# power_supply.net
KiCad netlist of a schematic drawn in Altium Designer
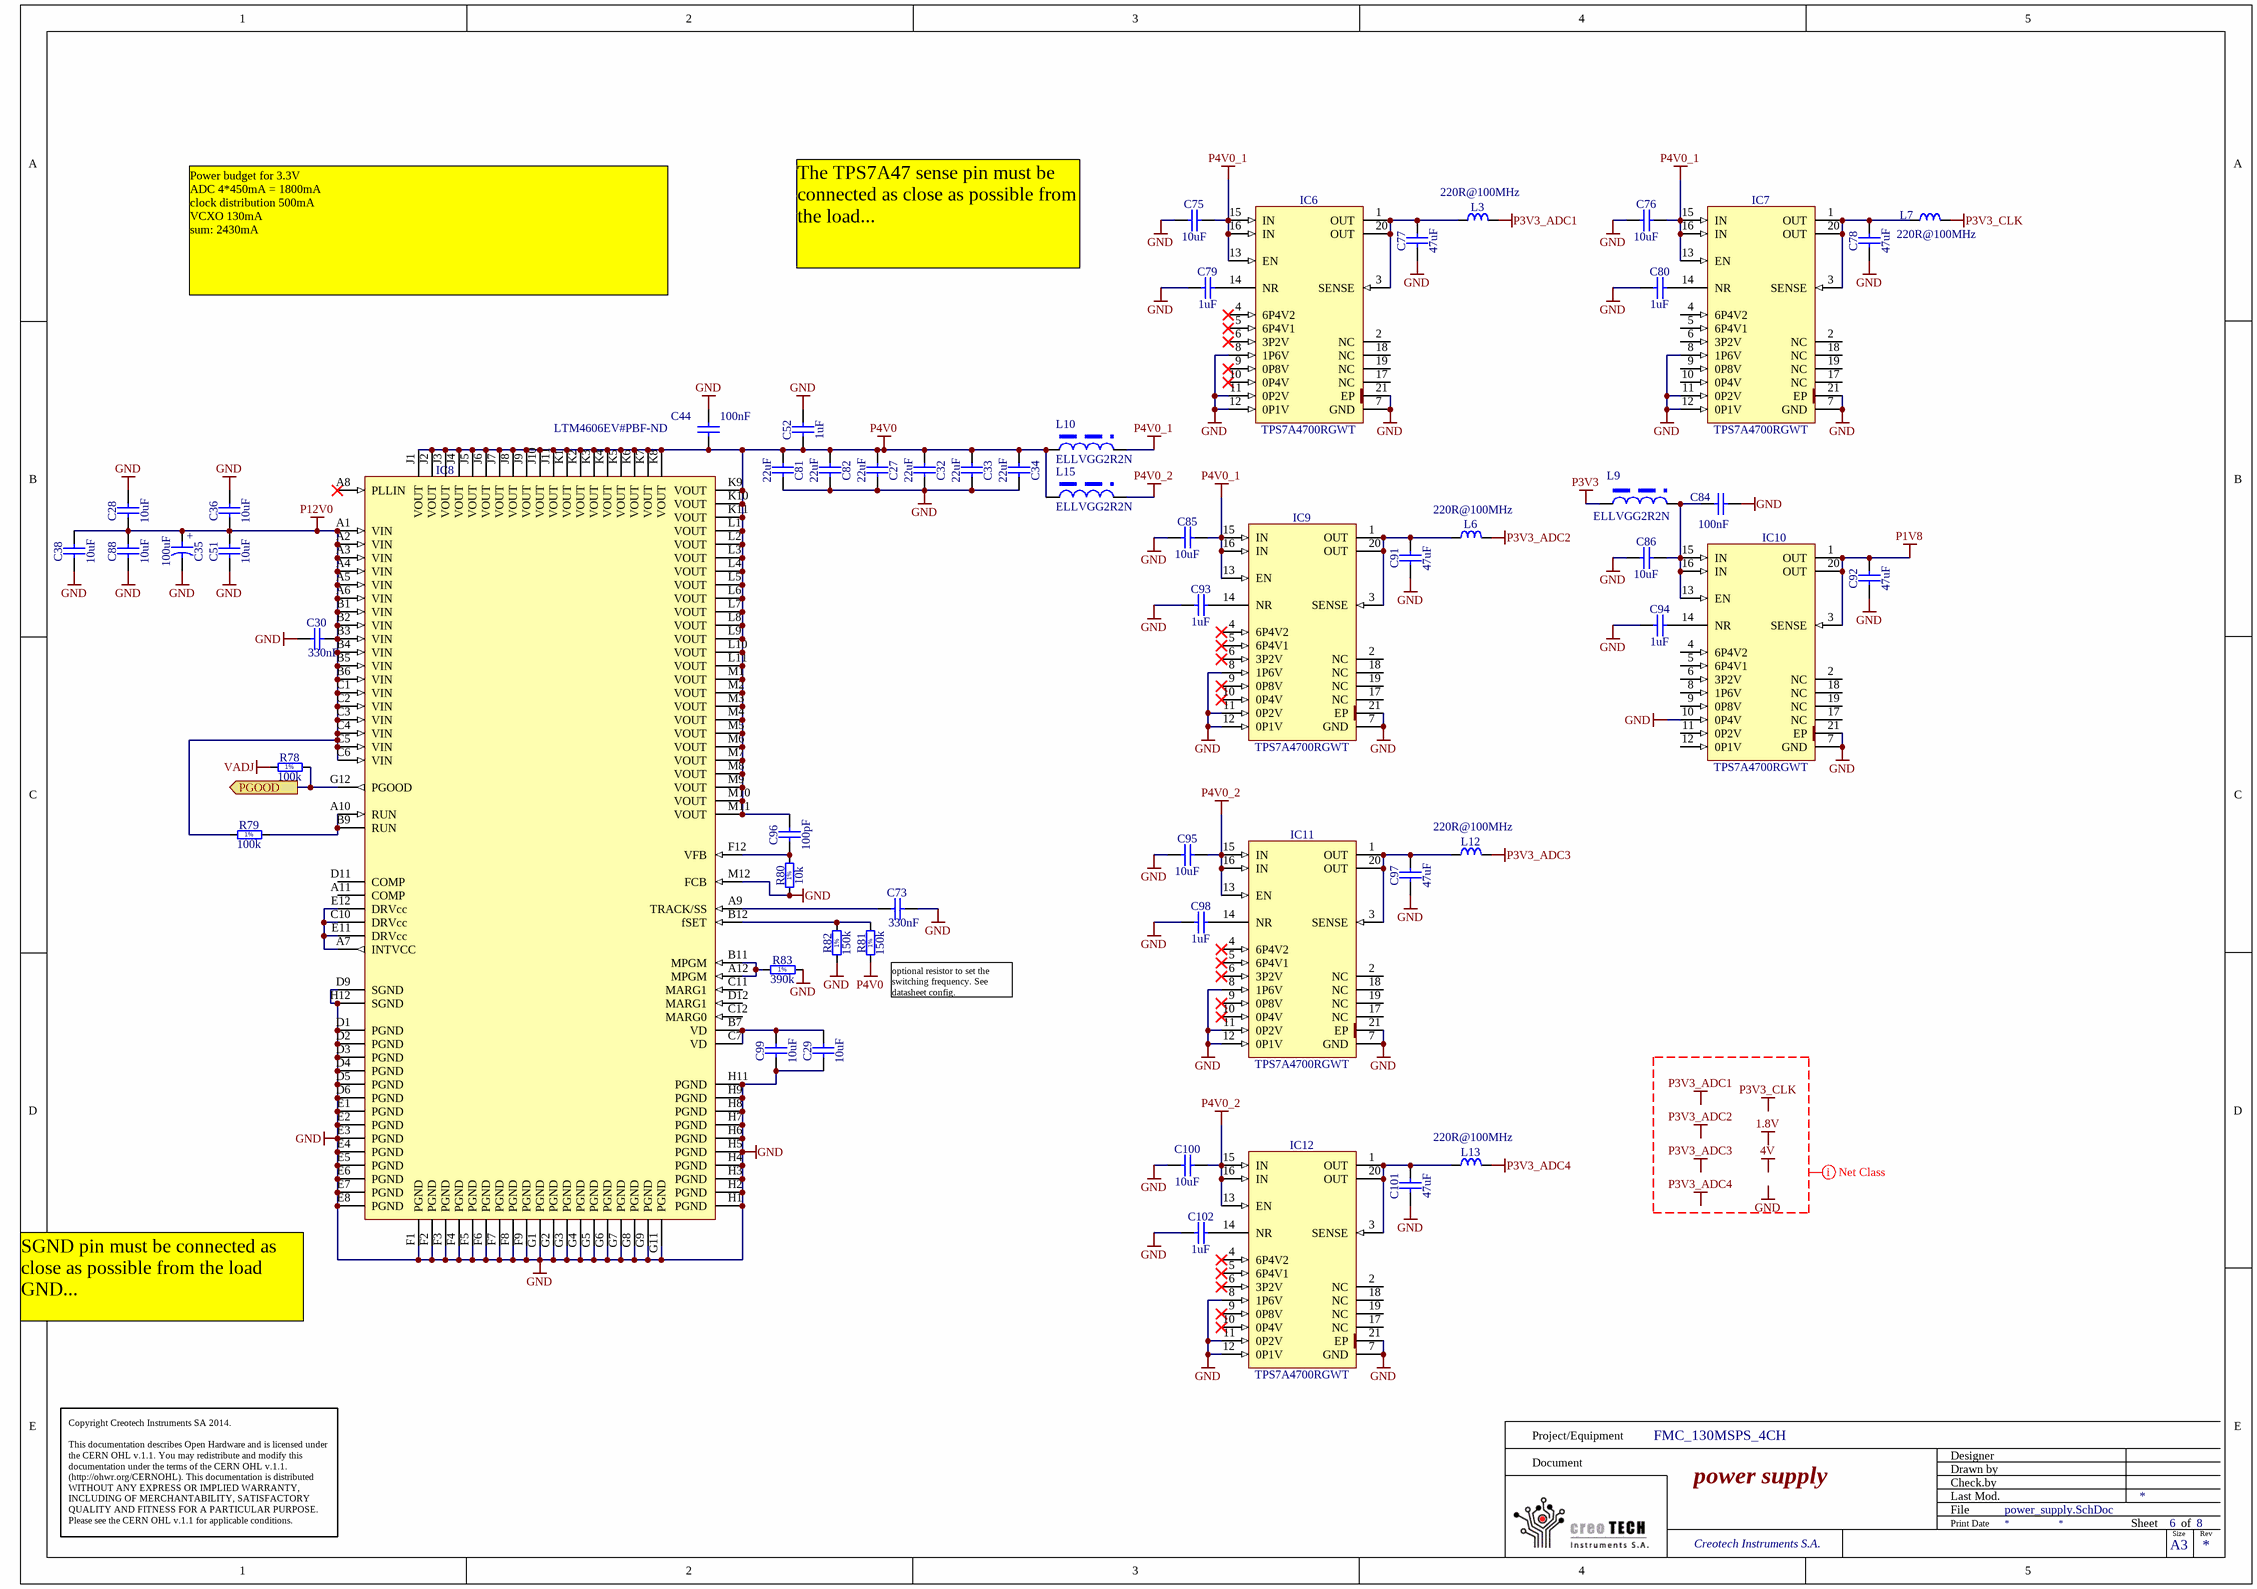
[diagram p0: power_supply.SchDoc]

(export (version "E")
  (design (tool "Eeschema 10.0.6"))
  (components
    (comp (ref "C27")
      (value "22uF")
      (footprint "CAPC3216X140N")
      (description "Non-polarised capacitor")
      (fields (field (name "PART NUMBER") "CC1206_22UF_6.3V_20%_X5R") (field (name "VOLTAGE") "6.3V"))
      (libsource (lib "Capacitors") (part "Capacitor - non polarized"))
    )
    (comp (ref "C28")
      (value "10uF")
      (footprint "CAPC2012X135N")
      (description "Non-polarised capacitor")
      (fields (field (name "PART NUMBER") "CC0805_10UF_16V_10%_X5R") (field (name "VOLTAGE") "16V"))
      (libsource (lib "Capacitors") (part "Capacitor - non polarized"))
    )
    (comp (ref "C29")
      (value "10uF")
      (footprint "CAPC2012X135N")
      (description "Non-polarised capacitor")
      (fields (field (name "PART NUMBER") "CC0805_10UF_16V_10%_X5R") (field (name "VOLTAGE") "16V"))
      (libsource (lib "Capacitors") (part "Capacitor - non polarized"))
    )
    (comp (ref "C30")
      (value "330nF")
      (footprint "CAPC1608X87N")
      (description "Non-polarised capacitor")
      (fields (field (name "PART NUMBER") "CC0603_330NF_16V_10%_X5R") (field (name "VOLTAGE") "16V"))
      (libsource (lib "Capacitors") (part "Capacitor - non polarized"))
    )
    (comp (ref "C32")
      (value "22uF")
      (footprint "CAPC3216X140N")
      (description "Non-polarised capacitor")
      (fields (field (name "PART NUMBER") "CC1206_22UF_6.3V_20%_X5R") (field (name "VOLTAGE") "6.3V"))
      (libsource (lib "Capacitors") (part "Capacitor - non polarized"))
    )
    (comp (ref "C33")
      (value "22uF")
      (footprint "CAPC3216X140N")
      (description "Non-polarised capacitor")
      (fields (field (name "PART NUMBER") "CC1206_22UF_6.3V_20%_X5R") (field (name "VOLTAGE") "6.3V"))
      (libsource (lib "Capacitors") (part "Capacitor - non polarized"))
    )
    (comp (ref "C34")
      (value "22uF")
      (footprint "CAPC3216X140N")
      (description "Non-polarised capacitor")
      (fields (field (name "PART NUMBER") "CC1206_22UF_6.3V_20%_X5R") (field (name "VOLTAGE") "6.3V"))
      (libsource (lib "Capacitors") (part "Capacitor - non polarized"))
    )
    (comp (ref "C35")
      (value "100uF")
      (footprint "CAPMP7343X310N")
      (description "Polarised capacitor")
      (fields (field (name "PART NUMBER") "CTE7343-31_100UF_20V_10%") (field (name "VOLTAGE") "20V"))
      (libsource (lib "Capacitors") (part "Capacitor - polarized"))
    )
    (comp (ref "C36")
      (value "10uF")
      (footprint "CAPC2012X135N")
      (description "Non-polarised capacitor")
      (fields (field (name "PART NUMBER") "CC0805_10UF_16V_10%_X5R") (field (name "VOLTAGE") "16V"))
      (libsource (lib "Capacitors") (part "Capacitor - non polarized"))
    )
    (comp (ref "C38")
      (value "10uF")
      (footprint "CAPC2012X135N")
      (description "Non-polarised capacitor")
      (fields (field (name "PART NUMBER") "CC0805_10UF_16V_10%_X5R") (field (name "VOLTAGE") "16V"))
      (libsource (lib "Capacitors") (part "Capacitor - non polarized"))
    )
    (comp (ref "C44")
      (value "100nF")
      (footprint "CAPC0603X33N")
      (description "Non-polarised capacitor")
      (fields (field (name "PART NUMBER") "CC0201_100NF_6.3V_10%_X5R") (field (name "VOLTAGE") "6.3V"))
      (libsource (lib "Capacitors") (part "Capacitor - non polarized"))
    )
    (comp (ref "C51")
      (value "10uF")
      (footprint "CAPC2012X135N")
      (description "Non-polarised capacitor")
      (fields (field (name "PART NUMBER") "CC0805_10UF_16V_10%_X5R") (field (name "VOLTAGE") "16V"))
      (libsource (lib "Capacitors") (part "Capacitor - non polarized"))
    )
    (comp (ref "C52")
      (value "1uF")
      (footprint "CAPC1608X87N")
      (description "Non-polarised capacitor")
      (fields (field (name "PART NUMBER") "CC0603_1UF_25V_10%_X7R") (field (name "VOLTAGE") "25V"))
      (libsource (lib "Capacitors") (part "Capacitor - non polarized"))
    )
    (comp (ref "C73")
      (value "330nF")
      (footprint "CAPC1608X87N")
      (description "Non-polarised capacitor")
      (fields (field (name "PART NUMBER") "CC0603_330NF_16V_10%_X5R") (field (name "VOLTAGE") "16V"))
      (libsource (lib "Capacitors") (part "Capacitor - non polarized"))
    )
    (comp (ref "C75")
      (value "10uF")
      (footprint "CAPC2012X135N")
      (description "Non-polarised capacitor")
      (fields (field (name "PART NUMBER") "CC0805_10UF_10V_10%_X7R") (field (name "VOLTAGE") "10V"))
      (libsource (lib "Capacitors") (part "Capacitor - non polarized"))
    )
    (comp (ref "C76")
      (value "10uF")
      (footprint "CAPC2012X135N")
      (description "Non-polarised capacitor")
      (fields (field (name "PART NUMBER") "CC0805_10UF_10V_10%_X7R") (field (name "VOLTAGE") "10V"))
      (libsource (lib "Capacitors") (part "Capacitor - non polarized"))
    )
    (comp (ref "C77")
      (value "47uF")
      (footprint "CAPC2012X140N")
      (description "Non-polarised capacitor")
      (fields (field (name "PART NUMBER") "CC0805_47UF_6.3V_20%_X5R") (field (name "VOLTAGE") "6.3V"))
      (libsource (lib "Capacitors") (part "Capacitor - non polarized"))
    )
    (comp (ref "C78")
      (value "47uF")
      (footprint "CAPC2012X140N")
      (description "Non-polarised capacitor")
      (fields (field (name "PART NUMBER") "CC0805_47UF_6.3V_20%_X5R") (field (name "VOLTAGE") "6.3V"))
      (libsource (lib "Capacitors") (part "Capacitor - non polarized"))
    )
    (comp (ref "C79")
      (value "1uF")
      (footprint "CAPC1608X87N")
      (description "Non-polarised capacitor")
      (fields (field (name "PART NUMBER") "CC0603_1UF_25V_10%_X7R") (field (name "VOLTAGE") "25V"))
      (libsource (lib "Capacitors") (part "Capacitor - non polarized"))
    )
    (comp (ref "C80")
      (value "1uF")
      (footprint "CAPC1608X87N")
      (description "Non-polarised capacitor")
      (fields (field (name "PART NUMBER") "CC0603_1UF_25V_10%_X7R") (field (name "VOLTAGE") "25V"))
      (libsource (lib "Capacitors") (part "Capacitor - non polarized"))
    )
    (comp (ref "C81")
      (value "22uF")
      (footprint "CAPC3216X140N")
      (description "Non-polarised capacitor")
      (fields (field (name "PART NUMBER") "CC1206_22UF_6.3V_20%_X5R") (field (name "VOLTAGE") "6.3V"))
      (libsource (lib "Capacitors") (part "Capacitor - non polarized"))
    )
    (comp (ref "C82")
      (value "22uF")
      (footprint "CAPC3216X140N")
      (description "Non-polarised capacitor")
      (fields (field (name "PART NUMBER") "CC1206_22UF_6.3V_20%_X5R") (field (name "VOLTAGE") "6.3V"))
      (libsource (lib "Capacitors") (part "Capacitor - non polarized"))
    )
    (comp (ref "C84")
      (value "100nF")
      (footprint "CAPC0603X33N")
      (description "Non-polarised capacitor")
      (fields (field (name "PART NUMBER") "CC0201_100NF_6.3V_10%_X5R") (field (name "VOLTAGE") "6.3V"))
      (libsource (lib "Capacitors") (part "Capacitor - non polarized"))
    )
    (comp (ref "C85")
      (value "10uF")
      (footprint "CAPC2012X135N")
      (description "Non-polarised capacitor")
      (fields (field (name "PART NUMBER") "CC0805_10UF_10V_10%_X7R") (field (name "VOLTAGE") "10V"))
      (libsource (lib "Capacitors") (part "Capacitor - non polarized"))
    )
    (comp (ref "C86")
      (value "10uF")
      (footprint "CAPC2012X135N")
      (description "Non-polarised capacitor")
      (fields (field (name "PART NUMBER") "CC0805_10UF_10V_10%_X7R") (field (name "VOLTAGE") "10V"))
      (libsource (lib "Capacitors") (part "Capacitor - non polarized"))
    )
    (comp (ref "C88")
      (value "10uF")
      (footprint "CAPC2012X135N")
      (description "Non-polarised capacitor")
      (fields (field (name "PART NUMBER") "CC0805_10UF_16V_10%_X5R") (field (name "VOLTAGE") "16V"))
      (libsource (lib "Capacitors") (part "Capacitor - non polarized"))
    )
    (comp (ref "C91")
      (value "47uF")
      (footprint "CAPC2012X140N")
      (description "Non-polarised capacitor")
      (fields (field (name "PART NUMBER") "CC0805_47UF_6.3V_20%_X5R") (field (name "VOLTAGE") "6.3V"))
      (libsource (lib "Capacitors") (part "Capacitor - non polarized"))
    )
    (comp (ref "C92")
      (value "47uF")
      (footprint "CAPC2012X140N")
      (description "Non-polarised capacitor")
      (fields (field (name "PART NUMBER") "CC0805_47UF_6.3V_20%_X5R") (field (name "VOLTAGE") "6.3V"))
      (libsource (lib "Capacitors") (part "Capacitor - non polarized"))
    )
    (comp (ref "C93")
      (value "1uF")
      (footprint "CAPC1608X87N")
      (description "Non-polarised capacitor")
      (fields (field (name "PART NUMBER") "CC0603_1UF_25V_10%_X7R") (field (name "VOLTAGE") "25V"))
      (libsource (lib "Capacitors") (part "Capacitor - non polarized"))
    )
    (comp (ref "C94")
      (value "1uF")
      (footprint "CAPC1608X87N")
      (description "Non-polarised capacitor")
      (fields (field (name "PART NUMBER") "CC0603_1UF_25V_10%_X7R") (field (name "VOLTAGE") "25V"))
      (libsource (lib "Capacitors") (part "Capacitor - non polarized"))
    )
    (comp (ref "C95")
      (value "10uF")
      (footprint "CAPC2012X135N")
      (description "Non-polarised capacitor")
      (fields (field (name "PART NUMBER") "CC0805_10UF_10V_10%_X7R") (field (name "VOLTAGE") "10V"))
      (libsource (lib "Capacitors") (part "Capacitor - non polarized"))
    )
    (comp (ref "C96")
      (value "100pF")
      (footprint "CAPC1005X55N")
      (description "Non-polarised capacitor")
      (fields (field (name "PART NUMBER") "CC0402_100PF_50V_5%_NP0") (field (name "VOLTAGE") "50V"))
      (libsource (lib "Capacitors") (part "Capacitor - non polarized"))
    )
    (comp (ref "C97")
      (value "47uF")
      (footprint "CAPC2012X140N")
      (description "Non-polarised capacitor")
      (fields (field (name "PART NUMBER") "CC0805_47UF_6.3V_20%_X5R") (field (name "VOLTAGE") "6.3V"))
      (libsource (lib "Capacitors") (part "Capacitor - non polarized"))
    )
    (comp (ref "C98")
      (value "1uF")
      (footprint "CAPC1608X87N")
      (description "Non-polarised capacitor")
      (fields (field (name "PART NUMBER") "CC0603_1UF_25V_10%_X7R") (field (name "VOLTAGE") "25V"))
      (libsource (lib "Capacitors") (part "Capacitor - non polarized"))
    )
    (comp (ref "C99")
      (value "10uF")
      (footprint "CAPC2012X135N")
      (description "Non-polarised capacitor")
      (fields (field (name "PART NUMBER") "CC0805_10UF_16V_10%_X5R") (field (name "VOLTAGE") "16V"))
      (libsource (lib "Capacitors") (part "Capacitor - non polarized"))
    )
    (comp (ref "C100")
      (value "10uF")
      (footprint "CAPC2012X135N")
      (description "Non-polarised capacitor")
      (fields (field (name "PART NUMBER") "CC0805_10UF_10V_10%_X7R") (field (name "VOLTAGE") "10V"))
      (libsource (lib "Capacitors") (part "Capacitor - non polarized"))
    )
    (comp (ref "C101")
      (value "47uF")
      (footprint "CAPC2012X140N")
      (description "Non-polarised capacitor")
      (fields (field (name "PART NUMBER") "CC0805_47UF_6.3V_20%_X5R") (field (name "VOLTAGE") "6.3V"))
      (libsource (lib "Capacitors") (part "Capacitor - non polarized"))
    )
    (comp (ref "C102")
      (value "1uF")
      (footprint "CAPC1608X87N")
      (description "Non-polarised capacitor")
      (fields (field (name "PART NUMBER") "CC0603_1UF_25V_10%_X7R") (field (name "VOLTAGE") "25V"))
      (libsource (lib "Capacitors") (part "Capacitor - non polarized"))
    )
    (comp (ref "IC6")
      (value "TPS7A4700RGWT")
      (footprint "QFN65P500X500X100-21N-S325")
      (description "Low Noise (3uVrms), 1A, High Voltage Low-Dropout Linear Regulator")
      (fields (field (name "MANUFACTURER") "TEXAS INSTRUMENTS"))
      (libsource (lib "ICs And Semiconductors") (part "TPS7A4700RGW"))
    )
    (comp (ref "IC7")
      (value "TPS7A4700RGWT")
      (footprint "QFN65P500X500X100-21N-S325")
      (description "Low Noise (3uVrms), 1A, High Voltage Low-Dropout Linear Regulator")
      (fields (field (name "MANUFACTURER") "TEXAS INSTRUMENTS"))
      (libsource (lib "ICs And Semiconductors") (part "TPS7A4700RGW"))
    )
    (comp (ref "IC8")
      (value "LTM4606EV#PBF-ND")
      (footprint "LTM4606")
      (description "4.5V-20V To 0.6V-5V, Iout 6A DC/DC low EMI uModule")
      (fields (field (name "SUPPLIER PART NUMBER 1") "LTM4606EV#PBF-ND"))
      (libsource (lib "fmclib") (part "LTM4601"))
    )
    (comp (ref "IC9")
      (value "TPS7A4700RGWT")
      (footprint "QFN65P500X500X100-21N-S325")
      (description "Low Noise (3uVrms), 1A, High Voltage Low-Dropout Linear Regulator")
      (fields (field (name "MANUFACTURER") "TEXAS INSTRUMENTS"))
      (libsource (lib "ICs And Semiconductors") (part "TPS7A4700RGW"))
    )
    (comp (ref "IC10")
      (value "TPS7A4700RGWT")
      (footprint "QFN65P500X500X100-21N-S325")
      (description "Low Noise (3uVrms), 1A, High Voltage Low-Dropout Linear Regulator")
      (fields (field (name "MANUFACTURER") "TEXAS INSTRUMENTS"))
      (libsource (lib "ICs And Semiconductors") (part "TPS7A4700RGW"))
    )
    (comp (ref "IC11")
      (value "TPS7A4700RGWT")
      (footprint "QFN65P500X500X100-21N-S325")
      (description "Low Noise (3uVrms), 1A, High Voltage Low-Dropout Linear Regulator")
      (fields (field (name "MANUFACTURER") "TEXAS INSTRUMENTS"))
      (libsource (lib "ICs And Semiconductors") (part "TPS7A4700RGW"))
    )
    (comp (ref "IC12")
      (value "TPS7A4700RGWT")
      (footprint "QFN65P500X500X100-21N-S325")
      (description "Low Noise (3uVrms), 1A, High Voltage Low-Dropout Linear Regulator")
      (fields (field (name "MANUFACTURER") "TEXAS INSTRUMENTS"))
      (libsource (lib "ICs And Semiconductors") (part "TPS7A4700RGW"))
    )
    (comp (ref "L3")
      (value "220R@100MHz")
      (footprint "INDC2012X105N")
      (description "Inductor")
      (fields (field (name "PART NUMBER") "IND0805_MURATA_BLM21PG221SN1D") (field (name "POWER") "2A"))
      (libsource (lib "Inductors & Transformers") (part "Inductor"))
    )
    (comp (ref "L6")
      (value "220R@100MHz")
      (footprint "INDC2012X105N")
      (description "Inductor")
      (fields (field (name "PART NUMBER") "IND0805_MURATA_BLM21PG221SN1D") (field (name "POWER") "2A"))
      (libsource (lib "Inductors & Transformers") (part "Inductor"))
    )
    (comp (ref "L7")
      (value "220R@100MHz")
      (footprint "INDC2012X105N")
      (description "Inductor")
      (fields (field (name "PART NUMBER") "IND0805_MURATA_BLM21PG221SN1D") (field (name "POWER") "2A"))
      (libsource (lib "Inductors & Transformers") (part "Inductor"))
    )
    (comp (ref "L9")
      (value "ELLVGG2R2N")
      (footprint "L_ELLVGG2R2N")
      (description "2.2uH, 1.4A, 92mR Panasonic")
      (libsource (lib "LIBRARY_SCH") (part "L_CHOKE_ELLVGG"))
    )
    (comp (ref "L10")
      (value "ELLVGG2R2N")
      (footprint "L_ELLVGG2R2N")
      (description "2.2uH, 1.4A, 92mR Panasonic")
      (libsource (lib "LIBRARY_SCH") (part "L_CHOKE_ELLVGG"))
    )
    (comp (ref "L12")
      (value "220R@100MHz")
      (footprint "INDC2012X105N")
      (description "Inductor")
      (fields (field (name "PART NUMBER") "IND0805_MURATA_BLM21PG221SN1D") (field (name "POWER") "2A"))
      (libsource (lib "Inductors & Transformers") (part "Inductor"))
    )
    (comp (ref "L13")
      (value "220R@100MHz")
      (footprint "INDC2012X105N")
      (description "Inductor")
      (fields (field (name "PART NUMBER") "IND0805_MURATA_BLM21PG221SN1D") (field (name "POWER") "2A"))
      (libsource (lib "Inductors & Transformers") (part "Inductor"))
    )
    (comp (ref "L15")
      (value "ELLVGG2R2N")
      (footprint "L_ELLVGG2R2N")
      (description "2.2uH, 1.4A, 92mR Panasonic")
      (libsource (lib "LIBRARY_SCH") (part "L_CHOKE_ELLVGG"))
    )
    (comp (ref "R78")
      (value "100k")
      (footprint "RESC1005X40N")
      (description "Resistor - 1%")
      (fields (field (name "PART NUMBER") "R0402_100K_1%_0.0625W_100PPM") (field (name "POWER") "0.0625W"))
      (libsource (lib "Resistors") (part "Resistor - 1%"))
    )
    (comp (ref "R79")
      (value "100k")
      (footprint "RESC1005X40N")
      (description "Resistor - 1%")
      (fields (field (name "PART NUMBER") "R0402_100K_1%_0.0625W_100PPM") (field (name "POWER") "0.0625W"))
      (libsource (lib "Resistors") (part "Resistor - 1%"))
    )
    (comp (ref "R80")
      (value "10k")
      (footprint "RESC1005X40N")
      (description "Resistor - 1%")
      (fields (field (name "PART NUMBER") "R0402_10K_1%_0.0625W_100PPM") (field (name "POWER") "0.0625W"))
      (libsource (lib "") (part "Resistor - 1%_1"))
    )
    (comp (ref "R81")
      (value "150k")
      (footprint "RESC1005X40N")
      (description "Resistor - 1%")
      (fields (field (name "PART NUMBER") "R0402_150K_1%_0.0625W_100PPM") (field (name "POWER") "0.0625W"))
      (libsource (lib "Resistors") (part "Resistor - 1%"))
    )
    (comp (ref "R82")
      (value "150k")
      (footprint "RESC1005X40N")
      (description "Resistor - 1%")
      (fields (field (name "PART NUMBER") "R0402_150K_1%_0.0625W_100PPM") (field (name "POWER") "0.0625W"))
      (libsource (lib "Resistors") (part "Resistor - 1%"))
    )
    (comp (ref "R83")
      (value "390k")
      (footprint "RESC1005X40N")
      (description "Resistor - 1%")
      (fields (field (name "PART NUMBER") "R0402_390K_1%_0.0625W_100PPM") (field (name "POWER") "0.0625W"))
      (libsource (lib "Resistors") (part "Resistor - 1%"))
    )
  )
  (nets
    (net (code "1") (name "/PGOOD") (class "Default")
      (node (ref "IC8") (pin "G12") (pinfunction "PGOOD_G12") (pintype "output"))
      (node (ref "R78") (pin "2") (pinfunction "2_2") (pintype "passive"))
    )
    (net (code "4") (name "GND") (class "Default")
      (node (ref "C100") (pin "1") (pinfunction "1_1") (pintype "passive"))
      (node (ref "C101") (pin "1") (pinfunction "1_1") (pintype "passive"))
      (node (ref "C102") (pin "1") (pinfunction "1_1") (pintype "passive"))
      (node (ref "C27") (pin "2") (pinfunction "2_2") (pintype "passive"))
      (node (ref "C28") (pin "2") (pinfunction "2_2") (pintype "passive"))
      (node (ref "C29") (pin "1") (pinfunction "1_1") (pintype "passive"))
      (node (ref "C30") (pin "1") (pinfunction "1_1") (pintype "passive"))
      (node (ref "C32") (pin "2") (pinfunction "2_2") (pintype "passive"))
      (node (ref "C33") (pin "2") (pinfunction "2_2") (pintype "passive"))
      (node (ref "C34") (pin "2") (pinfunction "2_2") (pintype "passive"))
      (node (ref "C35") (pin "2") (pinfunction "2_2") (pintype "passive"))
      (node (ref "C36") (pin "2") (pinfunction "2_2") (pintype "passive"))
      (node (ref "C38") (pin "1") (pinfunction "1_1") (pintype "passive"))
      (node (ref "C44") (pin "1") (pinfunction "1_1") (pintype "passive"))
      (node (ref "C51") (pin "1") (pinfunction "1_1") (pintype "passive"))
      (node (ref "C52") (pin "2") (pinfunction "2_2") (pintype "passive"))
      (node (ref "C73") (pin "2") (pinfunction "2_2") (pintype "passive"))
      (node (ref "C75") (pin "1") (pinfunction "1_1") (pintype "passive"))
      (node (ref "C76") (pin "1") (pinfunction "1_1") (pintype "passive"))
      (node (ref "C77") (pin "1") (pinfunction "1_1") (pintype "passive"))
      (node (ref "C78") (pin "1") (pinfunction "1_1") (pintype "passive"))
      (node (ref "C79") (pin "1") (pinfunction "1_1") (pintype "passive"))
      (node (ref "C80") (pin "1") (pinfunction "1_1") (pintype "passive"))
      (node (ref "C81") (pin "2") (pinfunction "2_2") (pintype "passive"))
      (node (ref "C82") (pin "2") (pinfunction "2_2") (pintype "passive"))
      (node (ref "C84") (pin "1") (pinfunction "1_1") (pintype "passive"))
      (node (ref "C85") (pin "1") (pinfunction "1_1") (pintype "passive"))
      (node (ref "C86") (pin "1") (pinfunction "1_1") (pintype "passive"))
      (node (ref "C88") (pin "1") (pinfunction "1_1") (pintype "passive"))
      (node (ref "C91") (pin "1") (pinfunction "1_1") (pintype "passive"))
      (node (ref "C92") (pin "1") (pinfunction "1_1") (pintype "passive"))
      (node (ref "C93") (pin "1") (pinfunction "1_1") (pintype "passive"))
      (node (ref "C94") (pin "1") (pinfunction "1_1") (pintype "passive"))
      (node (ref "C95") (pin "1") (pinfunction "1_1") (pintype "passive"))
      (node (ref "C97") (pin "1") (pinfunction "1_1") (pintype "passive"))
      (node (ref "C98") (pin "1") (pinfunction "1_1") (pintype "passive"))
      (node (ref "C99") (pin "1") (pinfunction "1_1") (pintype "passive"))
      (node (ref "IC10") (pin "10") (pinfunction "0P4V_10") (pintype "input"))
      (node (ref "IC10") (pin "21") (pinfunction "EP_21") (pintype "power_in"))
      (node (ref "IC10") (pin "7") (pinfunction "GND_7") (pintype "power_in"))
      (node (ref "IC11") (pin "11") (pinfunction "0P2V_11") (pintype "input"))
      (node (ref "IC11") (pin "12") (pinfunction "0P1V_12") (pintype "input"))
      (node (ref "IC11") (pin "21") (pinfunction "EP_21") (pintype "power_in"))
      (node (ref "IC11") (pin "7") (pinfunction "GND_7") (pintype "power_in"))
      (node (ref "IC11") (pin "8") (pinfunction "1P6V_8") (pintype "input"))
      (node (ref "IC12") (pin "11") (pinfunction "0P2V_11") (pintype "input"))
      (node (ref "IC12") (pin "12") (pinfunction "0P1V_12") (pintype "input"))
      (node (ref "IC12") (pin "21") (pinfunction "EP_21") (pintype "power_in"))
      (node (ref "IC12") (pin "7") (pinfunction "GND_7") (pintype "power_in"))
      (node (ref "IC12") (pin "8") (pinfunction "1P6V_8") (pintype "input"))
      (node (ref "IC6") (pin "11") (pinfunction "0P2V_11") (pintype "input"))
      (node (ref "IC6") (pin "12") (pinfunction "0P1V_12") (pintype "input"))
      (node (ref "IC6") (pin "21") (pinfunction "EP_21") (pintype "power_in"))
      (node (ref "IC6") (pin "7") (pinfunction "GND_7") (pintype "power_in"))
      (node (ref "IC6") (pin "8") (pinfunction "1P6V_8") (pintype "input"))
      (node (ref "IC7") (pin "11") (pinfunction "0P2V_11") (pintype "input"))
      (node (ref "IC7") (pin "12") (pinfunction "0P1V_12") (pintype "input"))
      (node (ref "IC7") (pin "21") (pinfunction "EP_21") (pintype "power_in"))
      (node (ref "IC7") (pin "7") (pinfunction "GND_7") (pintype "power_in"))
      (node (ref "IC7") (pin "8") (pinfunction "1P6V_8") (pintype "input"))
      (node (ref "IC8") (pin "D1") (pinfunction "PGND_D1") (pintype "power_in"))
      (node (ref "IC8") (pin "D2") (pinfunction "PGND_D2") (pintype "power_in"))
      (node (ref "IC8") (pin "D3") (pinfunction "PGND_D3") (pintype "power_in"))
      (node (ref "IC8") (pin "D4") (pinfunction "PGND_D4") (pintype "power_in"))
      (node (ref "IC8") (pin "D5") (pinfunction "PGND_D5") (pintype "power_in"))
      (node (ref "IC8") (pin "D6") (pinfunction "PGND_D6") (pintype "power_in"))
      (node (ref "IC8") (pin "D9") (pinfunction "SGND_D9") (pintype "power_in"))
      (node (ref "IC8") (pin "E1") (pinfunction "PGND_E1") (pintype "power_in"))
      (node (ref "IC8") (pin "E2") (pinfunction "PGND_E2") (pintype "power_in"))
      (node (ref "IC8") (pin "E3") (pinfunction "PGND_E3") (pintype "power_in"))
      (node (ref "IC8") (pin "E4") (pinfunction "PGND_E4") (pintype "power_in"))
      (node (ref "IC8") (pin "E5") (pinfunction "PGND_E5") (pintype "power_in"))
      (node (ref "IC8") (pin "E6") (pinfunction "PGND_E6") (pintype "power_in"))
      (node (ref "IC8") (pin "E7") (pinfunction "PGND_E7") (pintype "power_in"))
      (node (ref "IC8") (pin "E8") (pinfunction "PGND_E8") (pintype "power_in"))
      (node (ref "IC8") (pin "F1") (pinfunction "PGND_F1") (pintype "power_in"))
      (node (ref "IC8") (pin "F2") (pinfunction "PGND_F2") (pintype "power_in"))
      (node (ref "IC8") (pin "F3") (pinfunction "PGND_F3") (pintype "power_in"))
      (node (ref "IC8") (pin "F4") (pinfunction "PGND_F4") (pintype "power_in"))
      (node (ref "IC8") (pin "F5") (pinfunction "PGND_F5") (pintype "power_in"))
      (node (ref "IC8") (pin "F6") (pinfunction "PGND_F6") (pintype "power_in"))
      (node (ref "IC8") (pin "F7") (pinfunction "PGND_F7") (pintype "power_in"))
      (node (ref "IC8") (pin "F8") (pinfunction "PGND_F8") (pintype "power_in"))
      (node (ref "IC8") (pin "F9") (pinfunction "PGND_F9") (pintype "power_in"))
      (node (ref "IC8") (pin "G1") (pinfunction "PGND_G1") (pintype "power_in"))
      (node (ref "IC8") (pin "G11") (pinfunction "PGND_G11") (pintype "power_in"))
      (node (ref "IC8") (pin "G2") (pinfunction "PGND_G2") (pintype "power_in"))
      (node (ref "IC8") (pin "G3") (pinfunction "PGND_G3") (pintype "power_in"))
      (node (ref "IC8") (pin "G4") (pinfunction "PGND_G4") (pintype "power_in"))
      (node (ref "IC8") (pin "G5") (pinfunction "PGND_G5") (pintype "power_in"))
      (node (ref "IC8") (pin "G6") (pinfunction "PGND_G6") (pintype "power_in"))
      (node (ref "IC8") (pin "G7") (pinfunction "PGND_G7") (pintype "power_in"))
      (node (ref "IC8") (pin "G8") (pinfunction "PGND_G8") (pintype "power_in"))
      (node (ref "IC8") (pin "G9") (pinfunction "PGND_G9") (pintype "power_in"))
      (node (ref "IC8") (pin "H1") (pinfunction "PGND_H1") (pintype "power_in"))
      (node (ref "IC8") (pin "H11") (pinfunction "PGND_H11") (pintype "passive"))
      (node (ref "IC8") (pin "H12") (pinfunction "SGND_H12") (pintype "power_in"))
      (node (ref "IC8") (pin "H2") (pinfunction "PGND_H2") (pintype "power_in"))
      (node (ref "IC8") (pin "H3") (pinfunction "PGND_H3") (pintype "power_in"))
      (node (ref "IC8") (pin "H4") (pinfunction "PGND_H4") (pintype "power_in"))
      (node (ref "IC8") (pin "H5") (pinfunction "PGND_H5") (pintype "power_in"))
      (node (ref "IC8") (pin "H6") (pinfunction "PGND_H6") (pintype "power_in"))
      (node (ref "IC8") (pin "H7") (pinfunction "PGND_H7") (pintype "power_in"))
      (node (ref "IC8") (pin "H8") (pinfunction "PGND_H8") (pintype "power_in"))
      (node (ref "IC8") (pin "H9") (pinfunction "PGND_H9") (pintype "power_in"))
      (node (ref "IC8") (pin "M12") (pinfunction "FCB_M12") (pintype "input"))
      (node (ref "IC9") (pin "11") (pinfunction "0P2V_11") (pintype "input"))
      (node (ref "IC9") (pin "12") (pinfunction "0P1V_12") (pintype "input"))
      (node (ref "IC9") (pin "21") (pinfunction "EP_21") (pintype "power_in"))
      (node (ref "IC9") (pin "7") (pinfunction "GND_7") (pintype "power_in"))
      (node (ref "IC9") (pin "8") (pinfunction "1P6V_8") (pintype "input"))
      (node (ref "R80") (pin "2") (pinfunction "2_2") (pintype "passive"))
      (node (ref "R82") (pin "1") (pinfunction "1_1") (pintype "passive"))
      (node (ref "R83") (pin "2") (pinfunction "2_2") (pintype "passive"))
    )
    (net (code "5") (name "Net-(C29-Pad2)") (class "Default")
      (node (ref "C29") (pin "2") (pinfunction "2_2") (pintype "passive"))
      (node (ref "C99") (pin "2") (pinfunction "2_2") (pintype "passive"))
      (node (ref "IC8") (pin "B7") (pinfunction "VD_B7") (pintype "passive"))
      (node (ref "IC8") (pin "C7") (pinfunction "VD_C7") (pintype "passive"))
    )
    (net (code "6") (name "Net-(IC6-NR)") (class "Default")
      (node (ref "C79") (pin "2") (pinfunction "2_2") (pintype "passive"))
      (node (ref "IC6") (pin "14") (pinfunction "NR_14") (pintype "passive"))
    )
    (net (code "7") (name "Net-(IC6-SENSE)") (class "Default")
      (node (ref "C77") (pin "2") (pinfunction "2_2") (pintype "passive"))
      (node (ref "IC6") (pin "1") (pinfunction "OUT_1") (pintype "power_in"))
      (node (ref "IC6") (pin "20") (pinfunction "OUT_20") (pintype "power_in"))
      (node (ref "IC6") (pin "3") (pinfunction "SENSE_3") (pintype "input"))
      (node (ref "L3") (pin "1") (pinfunction "1_1") (pintype "passive"))
    )
    (net (code "8") (name "Net-(IC7-NR)") (class "Default")
      (node (ref "C80") (pin "2") (pinfunction "2_2") (pintype "passive"))
      (node (ref "IC7") (pin "14") (pinfunction "NR_14") (pintype "passive"))
    )
    (net (code "9") (name "Net-(IC7-SENSE)") (class "Default")
      (node (ref "C78") (pin "2") (pinfunction "2_2") (pintype "passive"))
      (node (ref "IC7") (pin "1") (pinfunction "OUT_1") (pintype "power_in"))
      (node (ref "IC7") (pin "20") (pinfunction "OUT_20") (pintype "power_in"))
      (node (ref "IC7") (pin "3") (pinfunction "SENSE_3") (pintype "input"))
      (node (ref "L7") (pin "1") (pinfunction "1_1") (pintype "passive"))
    )
    (net (code "10") (name "Net-(IC8-INTVCC)") (class "Default")
      (node (ref "IC8") (pin "A7") (pinfunction "INTVCC_A7") (pintype "output"))
      (node (ref "IC8") (pin "C10") (pinfunction "DRVcc_C10") (pintype "power_in"))
      (node (ref "IC8") (pin "E11") (pinfunction "DRVcc_E11") (pintype "power_in"))
      (node (ref "IC8") (pin "E12") (pinfunction "DRVcc_E12") (pintype "power_in"))
    )
    (net (code "11") (name "Net-(IC8-MPGM-PadA12)") (class "Default")
      (node (ref "IC8") (pin "A12") (pinfunction "MPGM_A12") (pintype "input"))
      (node (ref "IC8") (pin "B11") (pinfunction "MPGM_B11") (pintype "input"))
      (node (ref "R83") (pin "1") (pinfunction "1_1") (pintype "passive"))
    )
    (net (code "12") (name "Net-(IC8-RUN-PadA10)") (class "Default")
      (node (ref "IC8") (pin "A10") (pinfunction "RUN_A10") (pintype "input"))
      (node (ref "IC8") (pin "B9") (pinfunction "RUN_B9") (pintype "open_collector"))
      (node (ref "R79") (pin "2") (pinfunction "2_2") (pintype "passive"))
    )
    (net (code "13") (name "Net-(IC8-TRACK{slash}SS)") (class "Default")
      (node (ref "C73") (pin "1") (pinfunction "1_1") (pintype "passive"))
      (node (ref "IC8") (pin "A9") (pinfunction "TRACK/SS_A9") (pintype "input"))
    )
    (net (code "14") (name "Net-(IC8-VFB)") (class "Default")
      (node (ref "C96") (pin "1") (pinfunction "1_1") (pintype "passive"))
      (node (ref "IC8") (pin "F12") (pinfunction "VFB_F12") (pintype "input"))
      (node (ref "R80") (pin "1") (pinfunction "1_1") (pintype "passive"))
    )
    (net (code "15") (name "Net-(IC8-fSET)") (class "Default")
      (node (ref "IC8") (pin "B12") (pinfunction "fSET_B12") (pintype "input"))
      (node (ref "R81") (pin "2") (pinfunction "2_2") (pintype "passive"))
      (node (ref "R82") (pin "2") (pinfunction "2_2") (pintype "passive"))
    )
    (net (code "16") (name "Net-(IC9-NR)") (class "Default")
      (node (ref "C93") (pin "2") (pinfunction "2_2") (pintype "passive"))
      (node (ref "IC9") (pin "14") (pinfunction "NR_14") (pintype "passive"))
    )
    (net (code "17") (name "Net-(IC9-SENSE)") (class "Default")
      (node (ref "C91") (pin "2") (pinfunction "2_2") (pintype "passive"))
      (node (ref "IC9") (pin "1") (pinfunction "OUT_1") (pintype "power_in"))
      (node (ref "IC9") (pin "20") (pinfunction "OUT_20") (pintype "power_in"))
      (node (ref "IC9") (pin "3") (pinfunction "SENSE_3") (pintype "input"))
      (node (ref "L6") (pin "1") (pinfunction "1_1") (pintype "passive"))
    )
    (net (code "18") (name "Net-(IC10-EN)") (class "Default")
      (node (ref "C84") (pin "2") (pinfunction "2_2") (pintype "passive"))
      (node (ref "C86") (pin "2") (pinfunction "2_2") (pintype "passive"))
      (node (ref "IC10") (pin "13") (pinfunction "EN_13") (pintype "input"))
      (node (ref "IC10") (pin "15") (pinfunction "IN_15") (pintype "input"))
      (node (ref "IC10") (pin "16") (pinfunction "IN_16") (pintype "input"))
      (node (ref "L9") (pin "2") (pintype "passive"))
    )
    (net (code "19") (name "Net-(IC10-NR)") (class "Default")
      (node (ref "C94") (pin "2") (pinfunction "2_2") (pintype "passive"))
      (node (ref "IC10") (pin "14") (pinfunction "NR_14") (pintype "passive"))
    )
    (net (code "20") (name "Net-(IC11-NR)") (class "Default")
      (node (ref "C98") (pin "2") (pinfunction "2_2") (pintype "passive"))
      (node (ref "IC11") (pin "14") (pinfunction "NR_14") (pintype "passive"))
    )
    (net (code "21") (name "Net-(IC11-SENSE)") (class "Default")
      (node (ref "C97") (pin "2") (pinfunction "2_2") (pintype "passive"))
      (node (ref "IC11") (pin "1") (pinfunction "OUT_1") (pintype "power_in"))
      (node (ref "IC11") (pin "20") (pinfunction "OUT_20") (pintype "power_in"))
      (node (ref "IC11") (pin "3") (pinfunction "SENSE_3") (pintype "input"))
      (node (ref "L12") (pin "1") (pinfunction "1_1") (pintype "passive"))
    )
    (net (code "22") (name "Net-(IC12-NR)") (class "Default")
      (node (ref "C102") (pin "2") (pinfunction "2_2") (pintype "passive"))
      (node (ref "IC12") (pin "14") (pinfunction "NR_14") (pintype "passive"))
    )
    (net (code "23") (name "Net-(IC12-SENSE)") (class "Default")
      (node (ref "C101") (pin "2") (pinfunction "2_2") (pintype "passive"))
      (node (ref "IC12") (pin "1") (pinfunction "OUT_1") (pintype "power_in"))
      (node (ref "IC12") (pin "20") (pinfunction "OUT_20") (pintype "power_in"))
      (node (ref "IC12") (pin "3") (pinfunction "SENSE_3") (pintype "input"))
      (node (ref "L13") (pin "1") (pinfunction "1_1") (pintype "passive"))
    )
    (net (code "24") (name "P1V8") (class "Default")
      (node (ref "C92") (pin "2") (pinfunction "2_2") (pintype "passive"))
      (node (ref "IC10") (pin "1") (pinfunction "OUT_1") (pintype "power_in"))
      (node (ref "IC10") (pin "20") (pinfunction "OUT_20") (pintype "power_in"))
      (node (ref "IC10") (pin "3") (pinfunction "SENSE_3") (pintype "input"))
    )
    (net (code "25") (name "P3V3") (class "Default") (node (ref "L9") (pin "1") (pintype "passive")))
    (net (code "26") (name "P3V3_ADC1") (class "Default")
      (node (ref "L3") (pin "2") (pinfunction "2_2") (pintype "passive"))
    )
    (net (code "27") (name "P3V3_ADC2") (class "Default")
      (node (ref "L6") (pin "2") (pinfunction "2_2") (pintype "passive"))
    )
    (net (code "28") (name "P3V3_ADC3") (class "Default")
      (node (ref "L12") (pin "2") (pinfunction "2_2") (pintype "passive"))
    )
    (net (code "29") (name "P3V3_ADC4") (class "Default")
      (node (ref "L13") (pin "2") (pinfunction "2_2") (pintype "passive"))
    )
    (net (code "30") (name "P3V3_CLK") (class "Default")
      (node (ref "L7") (pin "2") (pinfunction "2_2") (pintype "passive"))
    )
    (net (code "31") (name "P4V0") (class "Default")
      (node (ref "C27") (pin "1") (pinfunction "1_1") (pintype "passive"))
      (node (ref "C32") (pin "1") (pinfunction "1_1") (pintype "passive"))
      (node (ref "C33") (pin "1") (pinfunction "1_1") (pintype "passive"))
      (node (ref "C34") (pin "1") (pinfunction "1_1") (pintype "passive"))
      (node (ref "C44") (pin "2") (pinfunction "2_2") (pintype "passive"))
      (node (ref "C52") (pin "1") (pinfunction "1_1") (pintype "passive"))
      (node (ref "C81") (pin "1") (pinfunction "1_1") (pintype "passive"))
      (node (ref "C82") (pin "1") (pinfunction "1_1") (pintype "passive"))
      (node (ref "C96") (pin "2") (pinfunction "2_2") (pintype "passive"))
      (node (ref "IC8") (pin "J1") (pinfunction "VOUT_J1") (pintype "power_in"))
      (node (ref "IC8") (pin "J10") (pinfunction "VOUT_J10") (pintype "power_in"))
      (node (ref "IC8") (pin "J11") (pinfunction "VOUT_J11") (pintype "power_in"))
      (node (ref "IC8") (pin "J2") (pinfunction "VOUT_J2") (pintype "power_in"))
      (node (ref "IC8") (pin "J3") (pinfunction "VOUT_J3") (pintype "power_in"))
      (node (ref "IC8") (pin "J4") (pinfunction "VOUT_J4") (pintype "power_in"))
      (node (ref "IC8") (pin "J5") (pinfunction "VOUT_J5") (pintype "power_in"))
      (node (ref "IC8") (pin "J6") (pinfunction "VOUT_J6") (pintype "power_in"))
      (node (ref "IC8") (pin "J7") (pinfunction "VOUT_J7") (pintype "power_in"))
      (node (ref "IC8") (pin "J8") (pinfunction "VOUT_J8") (pintype "power_in"))
      (node (ref "IC8") (pin "J9") (pinfunction "VOUT_J9") (pintype "power_in"))
      (node (ref "IC8") (pin "K1") (pinfunction "VOUT_K1") (pintype "power_in"))
      (node (ref "IC8") (pin "K10") (pinfunction "VOUT_K10") (pintype "power_in"))
      (node (ref "IC8") (pin "K11") (pinfunction "VOUT_K11") (pintype "power_in"))
      (node (ref "IC8") (pin "K2") (pinfunction "VOUT_K2") (pintype "power_in"))
      (node (ref "IC8") (pin "K3") (pinfunction "VOUT_K3") (pintype "power_in"))
      (node (ref "IC8") (pin "K4") (pinfunction "VOUT_K4") (pintype "power_in"))
      (node (ref "IC8") (pin "K5") (pinfunction "VOUT_K5") (pintype "power_in"))
      (node (ref "IC8") (pin "K6") (pinfunction "VOUT_K6") (pintype "power_in"))
      (node (ref "IC8") (pin "K7") (pinfunction "VOUT_K7") (pintype "power_in"))
      (node (ref "IC8") (pin "K8") (pinfunction "VOUT_K8") (pintype "power_in"))
      (node (ref "IC8") (pin "K9") (pinfunction "VOUT_K9") (pintype "power_in"))
      (node (ref "IC8") (pin "L1") (pinfunction "VOUT_L1") (pintype "power_in"))
      (node (ref "IC8") (pin "L10") (pinfunction "VOUT_L10") (pintype "power_in"))
      (node (ref "IC8") (pin "L11") (pinfunction "VOUT_L11") (pintype "power_in"))
      (node (ref "IC8") (pin "L2") (pinfunction "VOUT_L2") (pintype "power_in"))
      (node (ref "IC8") (pin "L3") (pinfunction "VOUT_L3") (pintype "power_in"))
      (node (ref "IC8") (pin "L4") (pinfunction "VOUT_L4") (pintype "power_in"))
      (node (ref "IC8") (pin "L5") (pinfunction "VOUT_L5") (pintype "power_in"))
      (node (ref "IC8") (pin "L6") (pinfunction "VOUT_L6") (pintype "power_in"))
      (node (ref "IC8") (pin "L7") (pinfunction "VOUT_L7") (pintype "power_in"))
      (node (ref "IC8") (pin "L8") (pinfunction "VOUT_L8") (pintype "power_in"))
      (node (ref "IC8") (pin "L9") (pinfunction "VOUT_L9") (pintype "power_in"))
      (node (ref "IC8") (pin "M1") (pinfunction "VOUT_M1") (pintype "power_in"))
      (node (ref "IC8") (pin "M10") (pinfunction "VOUT_M10") (pintype "power_in"))
      (node (ref "IC8") (pin "M11") (pinfunction "VOUT_M11") (pintype "power_in"))
      (node (ref "IC8") (pin "M2") (pinfunction "VOUT_M2") (pintype "power_in"))
      (node (ref "IC8") (pin "M3") (pinfunction "VOUT_M3") (pintype "power_in"))
      (node (ref "IC8") (pin "M4") (pinfunction "VOUT_M4") (pintype "power_in"))
      (node (ref "IC8") (pin "M5") (pinfunction "VOUT_M5") (pintype "power_in"))
      (node (ref "IC8") (pin "M6") (pinfunction "VOUT_M6") (pintype "power_in"))
      (node (ref "IC8") (pin "M7") (pinfunction "VOUT_M7") (pintype "power_in"))
      (node (ref "IC8") (pin "M8") (pinfunction "VOUT_M8") (pintype "power_in"))
      (node (ref "IC8") (pin "M9") (pinfunction "VOUT_M9") (pintype "power_in"))
      (node (ref "L10") (pin "1") (pintype "passive"))
      (node (ref "L15") (pin "1") (pintype "passive"))
      (node (ref "R81") (pin "1") (pinfunction "1_1") (pintype "passive"))
    )
    (net (code "32") (name "P4V0_1") (class "Default")
      (node (ref "C75") (pin "2") (pinfunction "2_2") (pintype "passive"))
      (node (ref "C76") (pin "2") (pinfunction "2_2") (pintype "passive"))
      (node (ref "C85") (pin "2") (pinfunction "2_2") (pintype "passive"))
      (node (ref "IC6") (pin "13") (pinfunction "EN_13") (pintype "input"))
      (node (ref "IC6") (pin "15") (pinfunction "IN_15") (pintype "input"))
      (node (ref "IC6") (pin "16") (pinfunction "IN_16") (pintype "input"))
      (node (ref "IC7") (pin "13") (pinfunction "EN_13") (pintype "input"))
      (node (ref "IC7") (pin "15") (pinfunction "IN_15") (pintype "input"))
      (node (ref "IC7") (pin "16") (pinfunction "IN_16") (pintype "input"))
      (node (ref "IC9") (pin "13") (pinfunction "EN_13") (pintype "input"))
      (node (ref "IC9") (pin "15") (pinfunction "IN_15") (pintype "input"))
      (node (ref "IC9") (pin "16") (pinfunction "IN_16") (pintype "input"))
      (node (ref "L10") (pin "2") (pintype "passive"))
    )
    (net (code "33") (name "P4V0_2") (class "Default")
      (node (ref "C100") (pin "2") (pinfunction "2_2") (pintype "passive"))
      (node (ref "C95") (pin "2") (pinfunction "2_2") (pintype "passive"))
      (node (ref "IC11") (pin "13") (pinfunction "EN_13") (pintype "input"))
      (node (ref "IC11") (pin "15") (pinfunction "IN_15") (pintype "input"))
      (node (ref "IC11") (pin "16") (pinfunction "IN_16") (pintype "input"))
      (node (ref "IC12") (pin "13") (pinfunction "EN_13") (pintype "input"))
      (node (ref "IC12") (pin "15") (pinfunction "IN_15") (pintype "input"))
      (node (ref "IC12") (pin "16") (pinfunction "IN_16") (pintype "input"))
      (node (ref "L15") (pin "2") (pintype "passive"))
    )
    (net (code "34") (name "P12V0") (class "Default")
      (node (ref "C28") (pin "1") (pinfunction "1_1") (pintype "passive"))
      (node (ref "C30") (pin "2") (pinfunction "2_2") (pintype "passive"))
      (node (ref "C35") (pin "1") (pinfunction "1_1") (pintype "passive"))
      (node (ref "C36") (pin "1") (pinfunction "1_1") (pintype "passive"))
      (node (ref "C38") (pin "2") (pinfunction "2_2") (pintype "passive"))
      (node (ref "C51") (pin "2") (pinfunction "2_2") (pintype "passive"))
      (node (ref "C88") (pin "2") (pinfunction "2_2") (pintype "passive"))
      (node (ref "IC8") (pin "A1") (pinfunction "VIN_A1") (pintype "input"))
      (node (ref "IC8") (pin "A2") (pinfunction "VIN_A2") (pintype "input"))
      (node (ref "IC8") (pin "A3") (pinfunction "VIN_A3") (pintype "input"))
      (node (ref "IC8") (pin "A4") (pinfunction "VIN_A4") (pintype "input"))
      (node (ref "IC8") (pin "A5") (pinfunction "VIN_A5") (pintype "input"))
      (node (ref "IC8") (pin "A6") (pinfunction "VIN_A6") (pintype "input"))
      (node (ref "IC8") (pin "B1") (pinfunction "VIN_B1") (pintype "input"))
      (node (ref "IC8") (pin "B2") (pinfunction "VIN_B2") (pintype "input"))
      (node (ref "IC8") (pin "B3") (pinfunction "VIN_B3") (pintype "input"))
      (node (ref "IC8") (pin "B4") (pinfunction "VIN_B4") (pintype "input"))
      (node (ref "IC8") (pin "B5") (pinfunction "VIN_B5") (pintype "input"))
      (node (ref "IC8") (pin "B6") (pinfunction "VIN_B6") (pintype "input"))
      (node (ref "IC8") (pin "C1") (pinfunction "VIN_C1") (pintype "input"))
      (node (ref "IC8") (pin "C2") (pinfunction "VIN_C2") (pintype "input"))
      (node (ref "IC8") (pin "C3") (pinfunction "VIN_C3") (pintype "input"))
      (node (ref "IC8") (pin "C4") (pinfunction "VIN_C4") (pintype "input"))
      (node (ref "IC8") (pin "C5") (pinfunction "VIN_C5") (pintype "input"))
      (node (ref "IC8") (pin "C6") (pinfunction "VIN_C6") (pintype "input"))
      (node (ref "R79") (pin "1") (pinfunction "1_1") (pintype "passive"))
    )
    (net (code "35") (name "VADJ") (class "Default")
      (node (ref "R78") (pin "1") (pinfunction "1_1") (pintype "passive"))
    )
    (net (code "36") (name "unconnected-(IC6-0P4V-Pad10)") (class "Default")
      (node (ref "IC6") (pin "10") (pinfunction "0P4V_10") (pintype "input+no_connect"))
    )
    (net (code "37") (name "unconnected-(IC6-0P8V-Pad9)") (class "Default")
      (node (ref "IC6") (pin "9") (pinfunction "0P8V_9") (pintype "input+no_connect"))
    )
    (net (code "38") (name "unconnected-(IC6-3P2V-Pad6)") (class "Default")
      (node (ref "IC6") (pin "6") (pinfunction "3P2V_6") (pintype "input+no_connect"))
    )
    (net (code "39") (name "unconnected-(IC6-6P4V1-Pad5)") (class "Default")
      (node (ref "IC6") (pin "5") (pinfunction "6P4V1_5") (pintype "input+no_connect"))
    )
    (net (code "40") (name "unconnected-(IC6-6P4V2-Pad4)") (class "Default")
      (node (ref "IC6") (pin "4") (pinfunction "6P4V2_4") (pintype "input+no_connect"))
    )
    (net (code "41") (name "unconnected-(IC6-NC-Pad2)") (class "Default")
      (node (ref "IC6") (pin "2") (pinfunction "NC_2") (pintype "passive"))
    )
    (net (code "42") (name "unconnected-(IC6-NC-Pad17)") (class "Default")
      (node (ref "IC6") (pin "17") (pinfunction "NC_17") (pintype "passive"))
    )
    (net (code "43") (name "unconnected-(IC6-NC-Pad18)") (class "Default")
      (node (ref "IC6") (pin "18") (pinfunction "NC_18") (pintype "passive"))
    )
    (net (code "44") (name "unconnected-(IC6-NC-Pad19)") (class "Default")
      (node (ref "IC6") (pin "19") (pinfunction "NC_19") (pintype "passive"))
    )
    (net (code "45") (name "unconnected-(IC7-0P4V-Pad10)") (class "Default")
      (node (ref "IC7") (pin "10") (pinfunction "0P4V_10") (pintype "input"))
    )
    (net (code "46") (name "unconnected-(IC7-0P8V-Pad9)") (class "Default")
      (node (ref "IC7") (pin "9") (pinfunction "0P8V_9") (pintype "input"))
    )
    (net (code "47") (name "unconnected-(IC7-3P2V-Pad6)") (class "Default")
      (node (ref "IC7") (pin "6") (pinfunction "3P2V_6") (pintype "input"))
    )
    (net (code "48") (name "unconnected-(IC7-6P4V1-Pad5)") (class "Default")
      (node (ref "IC7") (pin "5") (pinfunction "6P4V1_5") (pintype "input"))
    )
    (net (code "49") (name "unconnected-(IC7-6P4V2-Pad4)") (class "Default")
      (node (ref "IC7") (pin "4") (pinfunction "6P4V2_4") (pintype "input"))
    )
    (net (code "50") (name "unconnected-(IC7-NC-Pad2)") (class "Default")
      (node (ref "IC7") (pin "2") (pinfunction "NC_2") (pintype "passive"))
    )
    (net (code "51") (name "unconnected-(IC7-NC-Pad17)") (class "Default")
      (node (ref "IC7") (pin "17") (pinfunction "NC_17") (pintype "passive"))
    )
    (net (code "52") (name "unconnected-(IC7-NC-Pad18)") (class "Default")
      (node (ref "IC7") (pin "18") (pinfunction "NC_18") (pintype "passive"))
    )
    (net (code "53") (name "unconnected-(IC7-NC-Pad19)") (class "Default")
      (node (ref "IC7") (pin "19") (pinfunction "NC_19") (pintype "passive"))
    )
    (net (code "54") (name "unconnected-(IC8-COMP-PadA11)") (class "Default")
      (node (ref "IC8") (pin "A11") (pinfunction "COMP_A11") (pintype "passive"))
    )
    (net (code "55") (name "unconnected-(IC8-COMP-PadD11)") (class "Default")
      (node (ref "IC8") (pin "D11") (pinfunction "COMP_D11") (pintype "passive"))
    )
    (net (code "56") (name "unconnected-(IC8-MARG0-PadC12)") (class "Default")
      (node (ref "IC8") (pin "C12") (pinfunction "MARG0_C12") (pintype "input"))
    )
    (net (code "57") (name "unconnected-(IC8-MARG1-PadC11)") (class "Default")
      (node (ref "IC8") (pin "C11") (pinfunction "MARG1_C11") (pintype "input"))
    )
    (net (code "58") (name "unconnected-(IC8-MARG1-PadD12)") (class "Default")
      (node (ref "IC8") (pin "D12") (pinfunction "MARG1_D12") (pintype "input"))
    )
    (net (code "59") (name "unconnected-(IC8-NC-PadJ12)") (class "Default")
      (node (ref "IC8") (pin "J12") (pinfunction "NC_J12") (pintype "passive"))
    )
    (net (code "60") (name "unconnected-(IC8-NC-PadK12)") (class "Default")
      (node (ref "IC8") (pin "K12") (pinfunction "NC_K12") (pintype "passive"))
    )
    (net (code "61") (name "unconnected-(IC8-NC-PadL12)") (class "Default")
      (node (ref "IC8") (pin "L12") (pinfunction "NC_L12") (pintype "passive"))
    )
    (net (code "62") (name "unconnected-(IC8-PLLIN-PadA8)") (class "Default")
      (node (ref "IC8") (pin "A8") (pinfunction "PLLIN_A8") (pintype "input+no_connect"))
    )
    (net (code "63") (name "unconnected-(IC9-0P4V-Pad10)") (class "Default")
      (node (ref "IC9") (pin "10") (pinfunction "0P4V_10") (pintype "input+no_connect"))
    )
    (net (code "64") (name "unconnected-(IC9-0P8V-Pad9)") (class "Default")
      (node (ref "IC9") (pin "9") (pinfunction "0P8V_9") (pintype "input+no_connect"))
    )
    (net (code "65") (name "unconnected-(IC9-3P2V-Pad6)") (class "Default")
      (node (ref "IC9") (pin "6") (pinfunction "3P2V_6") (pintype "input+no_connect"))
    )
    (net (code "66") (name "unconnected-(IC9-6P4V1-Pad5)") (class "Default")
      (node (ref "IC9") (pin "5") (pinfunction "6P4V1_5") (pintype "input+no_connect"))
    )
    (net (code "67") (name "unconnected-(IC9-6P4V2-Pad4)") (class "Default")
      (node (ref "IC9") (pin "4") (pinfunction "6P4V2_4") (pintype "input+no_connect"))
    )
    (net (code "68") (name "unconnected-(IC9-NC-Pad2)") (class "Default")
      (node (ref "IC9") (pin "2") (pinfunction "NC_2") (pintype "passive"))
    )
    (net (code "69") (name "unconnected-(IC9-NC-Pad17)") (class "Default")
      (node (ref "IC9") (pin "17") (pinfunction "NC_17") (pintype "passive"))
    )
    (net (code "70") (name "unconnected-(IC9-NC-Pad18)") (class "Default")
      (node (ref "IC9") (pin "18") (pinfunction "NC_18") (pintype "passive"))
    )
    (net (code "71") (name "unconnected-(IC9-NC-Pad19)") (class "Default")
      (node (ref "IC9") (pin "19") (pinfunction "NC_19") (pintype "passive"))
    )
    (net (code "72") (name "unconnected-(IC10-0P1V-Pad12)") (class "Default")
      (node (ref "IC10") (pin "12") (pinfunction "0P1V_12") (pintype "input"))
    )
    (net (code "73") (name "unconnected-(IC10-0P2V-Pad11)") (class "Default")
      (node (ref "IC10") (pin "11") (pinfunction "0P2V_11") (pintype "input"))
    )
    (net (code "74") (name "unconnected-(IC10-0P8V-Pad9)") (class "Default")
      (node (ref "IC10") (pin "9") (pinfunction "0P8V_9") (pintype "input"))
    )
    (net (code "75") (name "unconnected-(IC10-1P6V-Pad8)") (class "Default")
      (node (ref "IC10") (pin "8") (pinfunction "1P6V_8") (pintype "input"))
    )
    (net (code "76") (name "unconnected-(IC10-3P2V-Pad6)") (class "Default")
      (node (ref "IC10") (pin "6") (pinfunction "3P2V_6") (pintype "input"))
    )
    (net (code "77") (name "unconnected-(IC10-6P4V1-Pad5)") (class "Default")
      (node (ref "IC10") (pin "5") (pinfunction "6P4V1_5") (pintype "input"))
    )
    (net (code "78") (name "unconnected-(IC10-6P4V2-Pad4)") (class "Default")
      (node (ref "IC10") (pin "4") (pinfunction "6P4V2_4") (pintype "input"))
    )
    (net (code "79") (name "unconnected-(IC10-NC-Pad2)") (class "Default")
      (node (ref "IC10") (pin "2") (pinfunction "NC_2") (pintype "passive"))
    )
    (net (code "80") (name "unconnected-(IC10-NC-Pad17)") (class "Default")
      (node (ref "IC10") (pin "17") (pinfunction "NC_17") (pintype "passive"))
    )
    (net (code "81") (name "unconnected-(IC10-NC-Pad18)") (class "Default")
      (node (ref "IC10") (pin "18") (pinfunction "NC_18") (pintype "passive"))
    )
    (net (code "82") (name "unconnected-(IC10-NC-Pad19)") (class "Default")
      (node (ref "IC10") (pin "19") (pinfunction "NC_19") (pintype "passive"))
    )
    (net (code "83") (name "unconnected-(IC11-0P4V-Pad10)") (class "Default")
      (node (ref "IC11") (pin "10") (pinfunction "0P4V_10") (pintype "input+no_connect"))
    )
    (net (code "84") (name "unconnected-(IC11-0P8V-Pad9)") (class "Default")
      (node (ref "IC11") (pin "9") (pinfunction "0P8V_9") (pintype "input+no_connect"))
    )
    (net (code "85") (name "unconnected-(IC11-3P2V-Pad6)") (class "Default")
      (node (ref "IC11") (pin "6") (pinfunction "3P2V_6") (pintype "input+no_connect"))
    )
    (net (code "86") (name "unconnected-(IC11-6P4V1-Pad5)") (class "Default")
      (node (ref "IC11") (pin "5") (pinfunction "6P4V1_5") (pintype "input+no_connect"))
    )
    (net (code "87") (name "unconnected-(IC11-6P4V2-Pad4)") (class "Default")
      (node (ref "IC11") (pin "4") (pinfunction "6P4V2_4") (pintype "input+no_connect"))
    )
    (net (code "88") (name "unconnected-(IC11-NC-Pad2)") (class "Default")
      (node (ref "IC11") (pin "2") (pinfunction "NC_2") (pintype "passive"))
    )
    (net (code "89") (name "unconnected-(IC11-NC-Pad17)") (class "Default")
      (node (ref "IC11") (pin "17") (pinfunction "NC_17") (pintype "passive"))
    )
    (net (code "90") (name "unconnected-(IC11-NC-Pad18)") (class "Default")
      (node (ref "IC11") (pin "18") (pinfunction "NC_18") (pintype "passive"))
    )
    (net (code "91") (name "unconnected-(IC11-NC-Pad19)") (class "Default")
      (node (ref "IC11") (pin "19") (pinfunction "NC_19") (pintype "passive"))
    )
    (net (code "92") (name "unconnected-(IC12-0P4V-Pad10)") (class "Default")
      (node (ref "IC12") (pin "10") (pinfunction "0P4V_10") (pintype "input+no_connect"))
    )
    (net (code "93") (name "unconnected-(IC12-0P8V-Pad9)") (class "Default")
      (node (ref "IC12") (pin "9") (pinfunction "0P8V_9") (pintype "input+no_connect"))
    )
    (net (code "94") (name "unconnected-(IC12-3P2V-Pad6)") (class "Default")
      (node (ref "IC12") (pin "6") (pinfunction "3P2V_6") (pintype "input+no_connect"))
    )
    (net (code "95") (name "unconnected-(IC12-6P4V1-Pad5)") (class "Default")
      (node (ref "IC12") (pin "5") (pinfunction "6P4V1_5") (pintype "input+no_connect"))
    )
    (net (code "96") (name "unconnected-(IC12-6P4V2-Pad4)") (class "Default")
      (node (ref "IC12") (pin "4") (pinfunction "6P4V2_4") (pintype "input+no_connect"))
    )
    (net (code "97") (name "unconnected-(IC12-NC-Pad2)") (class "Default")
      (node (ref "IC12") (pin "2") (pinfunction "NC_2") (pintype "passive"))
    )
    (net (code "98") (name "unconnected-(IC12-NC-Pad17)") (class "Default")
      (node (ref "IC12") (pin "17") (pinfunction "NC_17") (pintype "passive"))
    )
    (net (code "99") (name "unconnected-(IC12-NC-Pad18)") (class "Default")
      (node (ref "IC12") (pin "18") (pinfunction "NC_18") (pintype "passive"))
    )
    (net (code "100") (name "unconnected-(IC12-NC-Pad19)") (class "Default")
      (node (ref "IC12") (pin "19") (pinfunction "NC_19") (pintype "passive"))
    )
  )
)
